# stm32_smart_teach.net
KiCad netlist of a schematic drawn in EasyEDA Pro
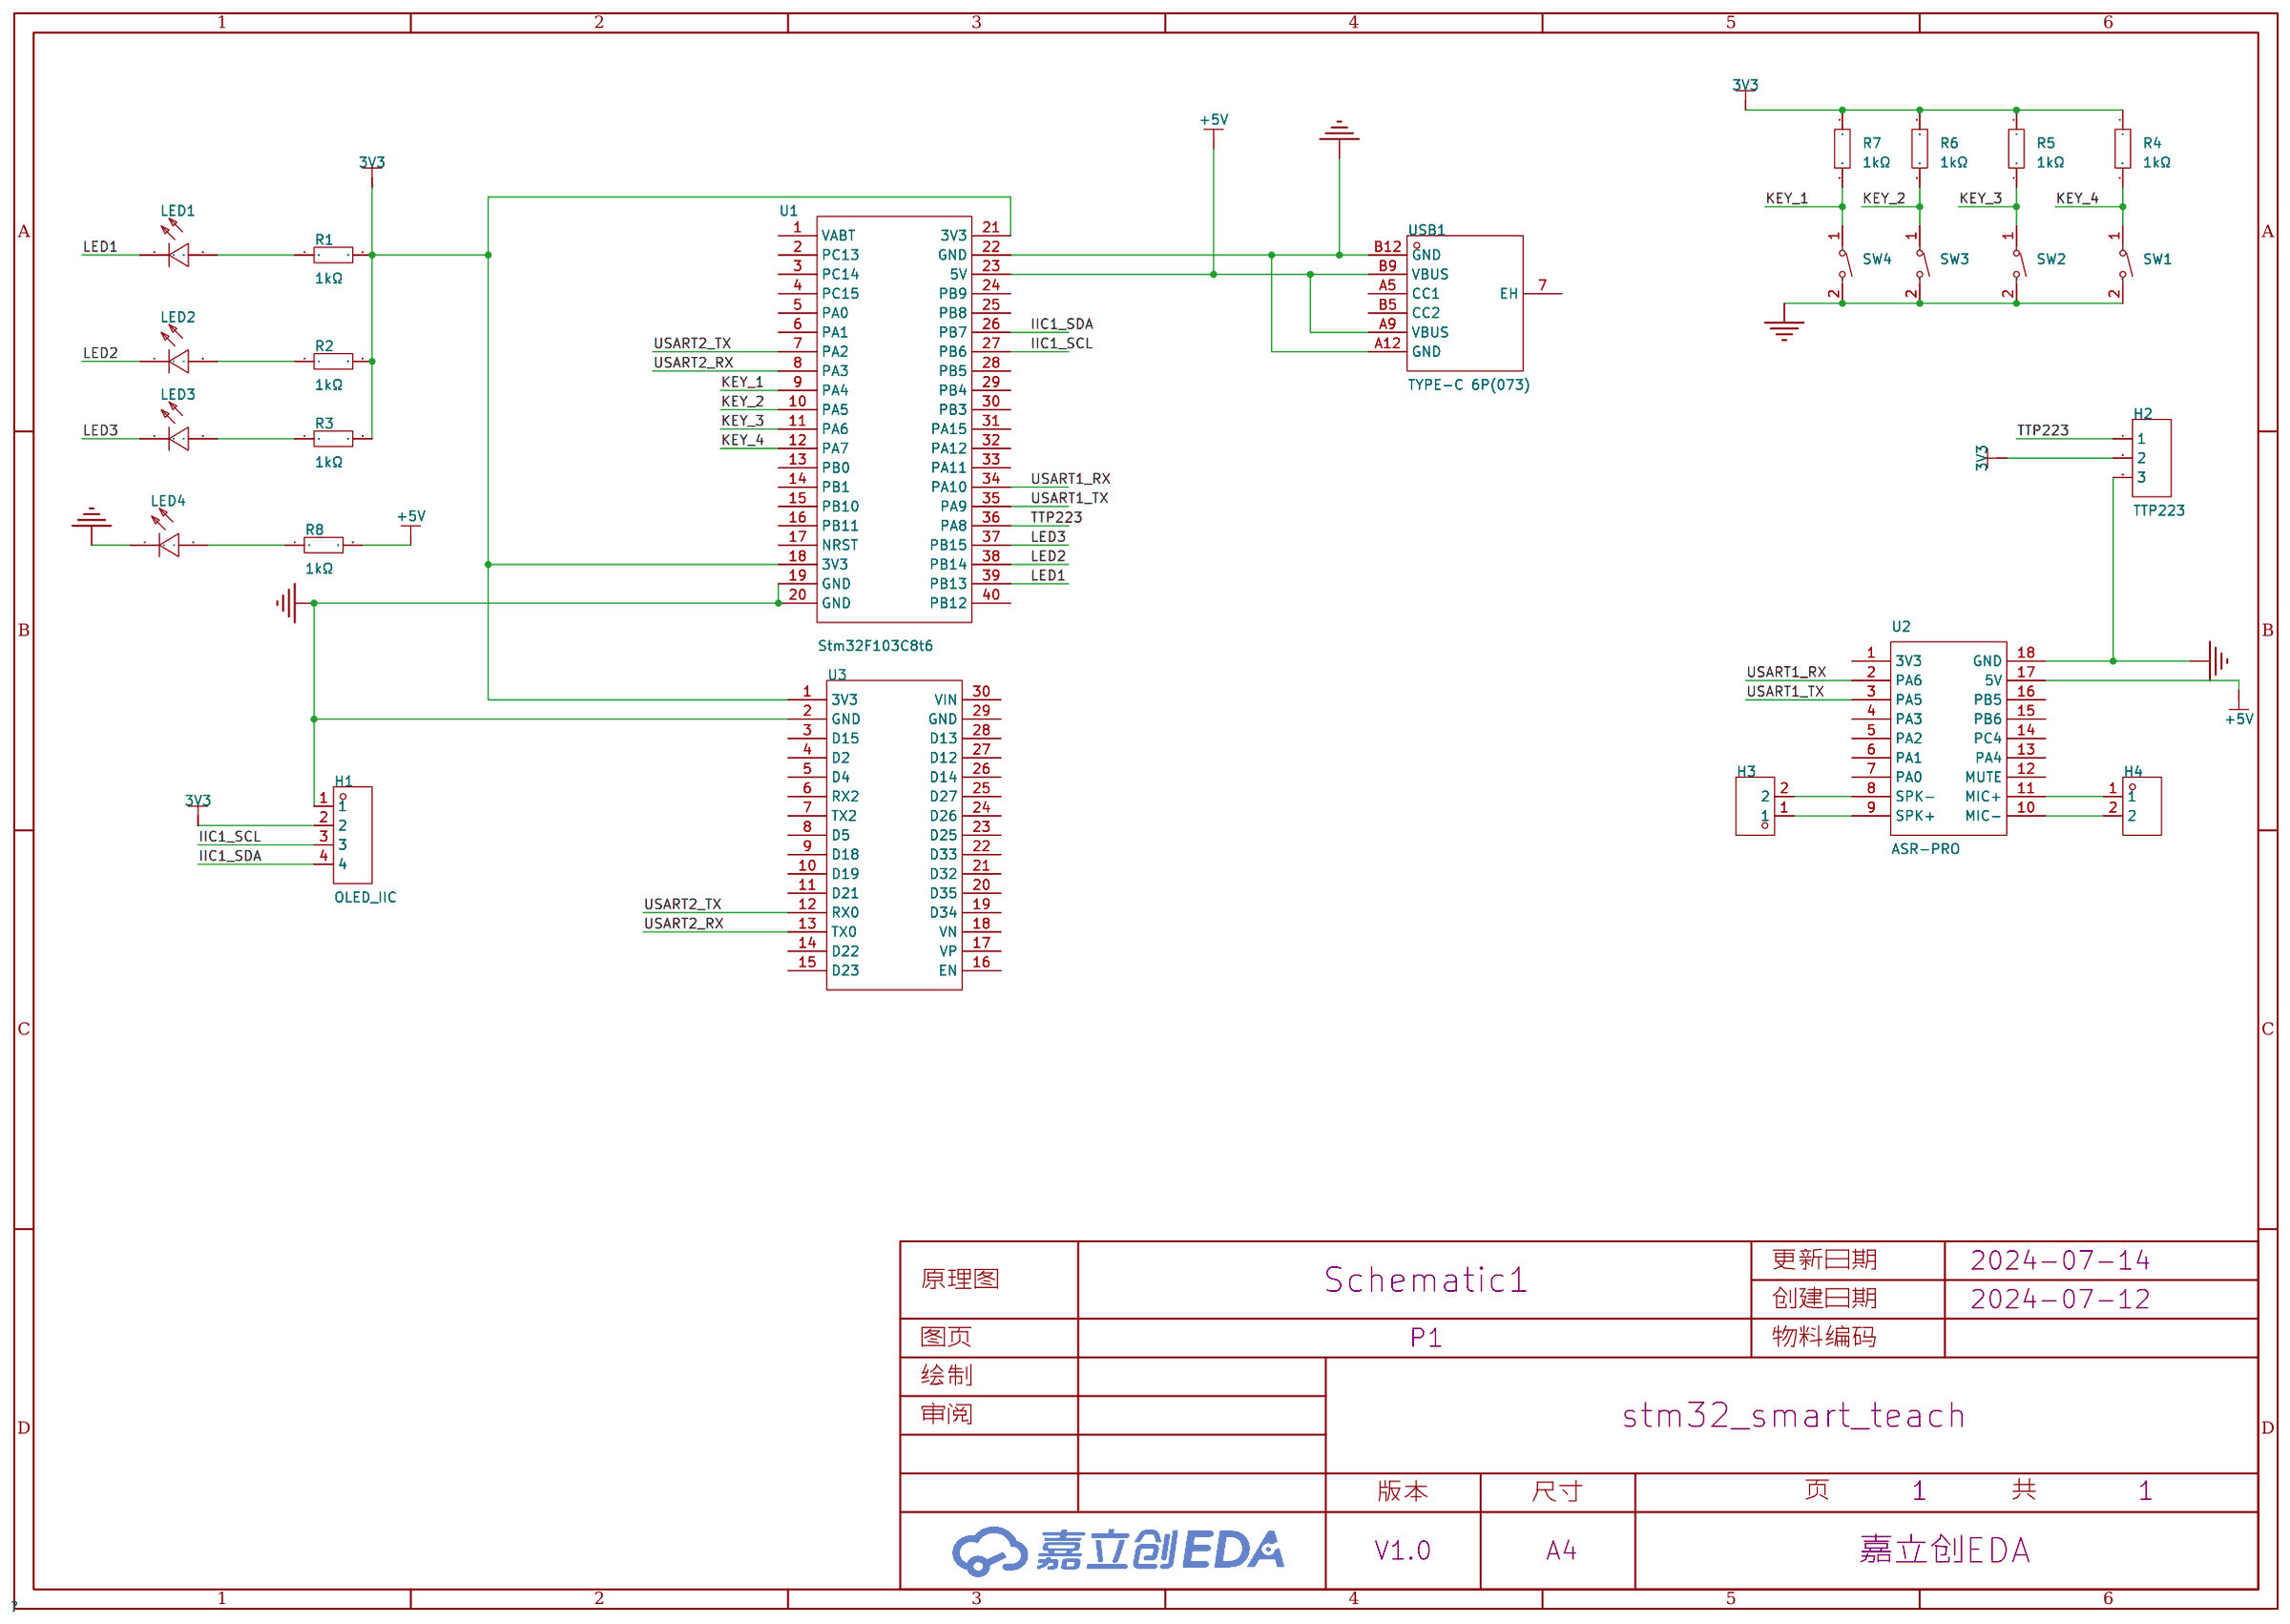
[diagram p0: schematic sheet]

(export (version "E")
  (design (tool "Eeschema 10.0.6"))
  (components
    (comp (ref "H1")
      (value "OLED_IIC")
      (footprint "easyedapro:HDR-TH_4P-P2.54-V-F")
      (fields (field (name "Manufacturer") "BOOMELE(博穆精密)"))
      (libsource (lib "easyedapro") (part "2.54-1*4P母"))
    )
    (comp (ref "H2")
      (value "TTP223")
      (footprint "easyedapro:HDR-TH_3P-P2.54-V-M-1")
      (fields (field (name "Manufacturer") "BOOMELE(博穆精密)"))
      (libsource (lib "easyedapro") (part "Header-Male-2.54_1x3"))
    )
    (comp (ref "H3")
      (value "PZ254V-11-02P")
      (footprint "easyedapro:HDR-TH_2P-P2.54-V-M")
      (fields (field (name "Manufacturer") "XFCN(兴飞)"))
      (libsource (lib "easyedapro") (part "PZ254V-11-02P"))
    )
    (comp (ref "H4")
      (value "PZ254V-11-02P")
      (footprint "easyedapro:HDR-TH_2P-P2.54-V-M")
      (fields (field (name "Manufacturer") "XFCN(兴飞)"))
      (libsource (lib "easyedapro") (part "PZ254V-11-02P"))
    )
    (comp (ref "LED1")
      (value "NCD0603R1")
      (footprint "easyedapro:LED0603-RD_RED")
      (fields (field (name "Manufacturer") "国星光电"))
      (libsource (lib "easyedapro") (part "FC-DA1608HRK-620D"))
    )
    (comp (ref "LED2")
      (value "NCD0603R1")
      (footprint "easyedapro:LED0603-RD_RED")
      (fields (field (name "Manufacturer") "国星光电"))
      (libsource (lib "easyedapro") (part "FC-DA1608HRK-620D"))
    )
    (comp (ref "LED3")
      (value "NCD0603R1")
      (footprint "easyedapro:LED0603-RD_RED")
      (fields (field (name "Manufacturer") "国星光电"))
      (libsource (lib "easyedapro") (part "FC-DA1608HRK-620D"))
    )
    (comp (ref "LED4")
      (value "NCD0603R1")
      (footprint "easyedapro:LED0603-RD_RED")
      (fields (field (name "Manufacturer") "国星光电"))
      (libsource (lib "easyedapro") (part "FC-DA1608HRK-620D"))
    )
    (comp (ref "R1")
      (value "1kΩ")
      (footprint "easyedapro:R0603")
      (description "电阻类型:厚膜电阻;阻值:1kΩ;精度:±1%;功率:100mW;最大工作电压:75V;温度系数:±100ppm/°C;")
      (fields
        (field (name "Manufacturer Part") "0603WAF1001T5E")
        (field (name "Manufacturer") "UNI-ROYAL(厚声)")
      )
      (libsource (lib "easyedapro") (part "0603WAF1001T5E"))
    )
    (comp (ref "R2")
      (value "1kΩ")
      (footprint "easyedapro:R0603")
      (description "电阻类型:厚膜电阻;阻值:1kΩ;精度:±1%;功率:100mW;最大工作电压:75V;温度系数:±100ppm/°C;")
      (fields
        (field (name "Manufacturer Part") "0603WAF1001T5E")
        (field (name "Manufacturer") "UNI-ROYAL(厚声)")
      )
      (libsource (lib "easyedapro") (part "0603WAF1001T5E"))
    )
    (comp (ref "R3")
      (value "1kΩ")
      (footprint "easyedapro:R0603")
      (description "电阻类型:厚膜电阻;阻值:1kΩ;精度:±1%;功率:100mW;最大工作电压:75V;温度系数:±100ppm/°C;")
      (fields
        (field (name "Manufacturer Part") "0603WAF1001T5E")
        (field (name "Manufacturer") "UNI-ROYAL(厚声)")
      )
      (libsource (lib "easyedapro") (part "0603WAF1001T5E"))
    )
    (comp (ref "R4")
      (value "1kΩ")
      (footprint "easyedapro:R0603")
      (description "电阻类型:厚膜电阻;阻值:1kΩ;精度:±1%;功率:100mW;最大工作电压:75V;温度系数:±100ppm/°C;")
      (fields
        (field (name "Manufacturer Part") "0603WAF1001T5E")
        (field (name "Manufacturer") "UNI-ROYAL(厚声)")
      )
      (libsource (lib "easyedapro") (part "0603WAF1001T5E"))
    )
    (comp (ref "R5")
      (value "1kΩ")
      (footprint "easyedapro:R0603")
      (description "电阻类型:厚膜电阻;阻值:1kΩ;精度:±1%;功率:100mW;最大工作电压:75V;温度系数:±100ppm/°C;")
      (fields
        (field (name "Manufacturer Part") "0603WAF1001T5E")
        (field (name "Manufacturer") "UNI-ROYAL(厚声)")
      )
      (libsource (lib "easyedapro") (part "0603WAF1001T5E"))
    )
    (comp (ref "R6")
      (value "1kΩ")
      (footprint "easyedapro:R0603")
      (description "电阻类型:厚膜电阻;阻值:1kΩ;精度:±1%;功率:100mW;最大工作电压:75V;温度系数:±100ppm/°C;")
      (fields
        (field (name "Manufacturer Part") "0603WAF1001T5E")
        (field (name "Manufacturer") "UNI-ROYAL(厚声)")
      )
      (libsource (lib "easyedapro") (part "0603WAF1001T5E"))
    )
    (comp (ref "R7")
      (value "1kΩ")
      (footprint "easyedapro:R0603")
      (description "电阻类型:厚膜电阻;阻值:1kΩ;精度:±1%;功率:100mW;最大工作电压:75V;温度系数:±100ppm/°C;")
      (fields
        (field (name "Manufacturer Part") "0603WAF1001T5E")
        (field (name "Manufacturer") "UNI-ROYAL(厚声)")
      )
      (libsource (lib "easyedapro") (part "0603WAF1001T5E"))
    )
    (comp (ref "R8")
      (value "1kΩ")
      (footprint "easyedapro:R0603")
      (description "电阻类型:厚膜电阻;阻值:1kΩ;精度:±1%;功率:100mW;最大工作电压:75V;温度系数:±100ppm/°C;")
      (fields
        (field (name "Manufacturer Part") "0603WAF1001T5E")
        (field (name "Manufacturer") "UNI-ROYAL(厚声)")
      )
      (libsource (lib "easyedapro") (part "0603WAF1001T5E"))
    )
    (comp (ref "SW1")
      (value "GT-TC060A-H025-L1S")
      (footprint "easyedapro:SW-SMD_L6.1-W3.5-LS8.0")
      (description "电路结构:单刀单掷;作用力:1.6N;安装方式:立贴;带支架:不带;触点电流:50mA;额定电压(AC):12V;额定电压(DC):12V;绝缘电阻:100MΩ;带灯:无;机械寿命:10万次;")
      (fields (field (name "Manufacturer") "G-Switch(品赞)"))
      (libsource (lib "easyedapro") (part "GT-TC060A-H025-L1S"))
    )
    (comp (ref "SW2")
      (value "GT-TC060A-H025-L1S")
      (footprint "easyedapro:SW-SMD_L6.1-W3.5-LS8.0")
      (description "电路结构:单刀单掷;作用力:1.6N;安装方式:立贴;带支架:不带;触点电流:50mA;额定电压(AC):12V;额定电压(DC):12V;绝缘电阻:100MΩ;带灯:无;机械寿命:10万次;")
      (fields (field (name "Manufacturer") "G-Switch(品赞)"))
      (libsource (lib "easyedapro") (part "GT-TC060A-H025-L1S"))
    )
    (comp (ref "SW3")
      (value "GT-TC060A-H025-L1S")
      (footprint "easyedapro:SW-SMD_L6.1-W3.5-LS8.0")
      (description "电路结构:单刀单掷;作用力:1.6N;安装方式:立贴;带支架:不带;触点电流:50mA;额定电压(AC):12V;额定电压(DC):12V;绝缘电阻:100MΩ;带灯:无;机械寿命:10万次;")
      (fields (field (name "Manufacturer") "G-Switch(品赞)"))
      (libsource (lib "easyedapro") (part "GT-TC060A-H025-L1S"))
    )
    (comp (ref "SW4")
      (value "GT-TC060A-H025-L1S")
      (footprint "easyedapro:SW-SMD_L6.1-W3.5-LS8.0")
      (description "电路结构:单刀单掷;作用力:1.6N;安装方式:立贴;带支架:不带;触点电流:50mA;额定电压(AC):12V;额定电压(DC):12V;绝缘电阻:100MΩ;带灯:无;机械寿命:10万次;")
      (fields (field (name "Manufacturer") "G-Switch(品赞)"))
      (libsource (lib "easyedapro") (part "GT-TC060A-H025-L1S"))
    )
    (comp (ref "U1") (value "Stm32F103C8t6") (libsource (lib "easyedapro") (part "stm32f103c8t6")))
    (comp (ref "U2") (value "ASR-PRO") (libsource (lib "easyedapro") (part "ASR-PRO")))
    (comp (ref "U3") (value "~") (libsource (lib "easyedapro") (part "esp32")))
    (comp (ref "USB1")
      (value "TYPE-C 6P(073)")
      (footprint "easyedapro:TYPE-C-SMD_TYPE-C-6P")
      (description "连接器类型:Type-C;标准:-;公母:母;端口数量:1;触点数量:6P;安装方式:卧贴;额定电流 - 电源:5A;工作温度范围:-25°C~+85°C;")
      (fields (field (name "Manufacturer") "SHOU HAN(首韩)"))
      (libsource (lib "easyedapro") (part "TYPE-C 6P(073)"))
    )
  )
  (nets
    (net (code "1") (name "+5V") (class "Default")
      (node (ref "R8") (pin "2") (pinfunction "2_2") (pintype "input"))
      (node (ref "U1") (pin "23") (pinfunction "5V_23") (pintype "input"))
      (node (ref "U2") (pin "17") (pinfunction "5V_17") (pintype "input"))
      (node (ref "USB1") (pin "A9") (pinfunction "VBUS_A9") (pintype "unspecified"))
      (node (ref "USB1") (pin "B9") (pinfunction "VBUS_B9") (pintype "unspecified"))
    )
    (net (code "2") (name "/IIC1_SCL") (class "Default")
      (node (ref "H1") (pin "3") (pinfunction "3_3") (pintype "unspecified"))
      (node (ref "U1") (pin "27") (pinfunction "PB6_27") (pintype "input"))
    )
    (net (code "3") (name "/IIC1_SDA") (class "Default")
      (node (ref "H1") (pin "4") (pinfunction "4_4") (pintype "unspecified"))
      (node (ref "U1") (pin "26") (pinfunction "PB7_26") (pintype "input"))
    )
    (net (code "4") (name "/KEY_1") (class "Default")
      (node (ref "R7") (pin "2") (pinfunction "2_2") (pintype "input"))
      (node (ref "SW4") (pin "1") (pinfunction "1_1") (pintype "unspecified"))
      (node (ref "U1") (pin "9") (pinfunction "PA4_9") (pintype "input"))
    )
    (net (code "5") (name "/KEY_2") (class "Default")
      (node (ref "R6") (pin "2") (pinfunction "2_2") (pintype "input"))
      (node (ref "SW3") (pin "1") (pinfunction "1_1") (pintype "unspecified"))
      (node (ref "U1") (pin "10") (pinfunction "PA5_10") (pintype "input"))
    )
    (net (code "6") (name "/KEY_3") (class "Default")
      (node (ref "R5") (pin "2") (pinfunction "2_2") (pintype "input"))
      (node (ref "SW2") (pin "1") (pinfunction "1_1") (pintype "unspecified"))
      (node (ref "U1") (pin "11") (pinfunction "PA6_11") (pintype "input"))
    )
    (net (code "7") (name "/KEY_4") (class "Default")
      (node (ref "R4") (pin "2") (pinfunction "2_2") (pintype "input"))
      (node (ref "SW1") (pin "1") (pinfunction "1_1") (pintype "unspecified"))
      (node (ref "U1") (pin "12") (pinfunction "PA7_12") (pintype "input"))
    )
    (net (code "8") (name "/LED1") (class "Default")
      (node (ref "LED1") (pin "1") (pinfunction "K_1") (pintype "input"))
      (node (ref "U1") (pin "39") (pinfunction "PB13_39") (pintype "input"))
    )
    (net (code "9") (name "/LED2") (class "Default")
      (node (ref "LED2") (pin "1") (pinfunction "K_1") (pintype "input"))
      (node (ref "U1") (pin "38") (pinfunction "PB14_38") (pintype "input"))
    )
    (net (code "10") (name "/LED3") (class "Default")
      (node (ref "LED3") (pin "1") (pinfunction "K_1") (pintype "input"))
      (node (ref "U1") (pin "37") (pinfunction "PB15_37") (pintype "input"))
    )
    (net (code "11") (name "/TTP223") (class "Default")
      (node (ref "H2") (pin "1") (pinfunction "1_1") (pintype "input"))
      (node (ref "U1") (pin "36") (pinfunction "PA8_36") (pintype "input"))
    )
    (net (code "12") (name "/USART1_RX") (class "Default")
      (node (ref "U1") (pin "34") (pinfunction "PA10_34") (pintype "input"))
      (node (ref "U2") (pin "2") (pinfunction "PA6_2") (pintype "input"))
    )
    (net (code "13") (name "/USART1_TX") (class "Default")
      (node (ref "U1") (pin "35") (pinfunction "PA9_35") (pintype "input"))
      (node (ref "U2") (pin "3") (pinfunction "PA5_3") (pintype "input"))
    )
    (net (code "14") (name "/USART2_RX") (class "Default")
      (node (ref "U1") (pin "8") (pinfunction "PA3_8") (pintype "input"))
      (node (ref "U3") (pin "13") (pinfunction "TX0_13") (pintype "input"))
    )
    (net (code "15") (name "/USART2_TX") (class "Default")
      (node (ref "U1") (pin "7") (pinfunction "PA2_7") (pintype "input"))
      (node (ref "U3") (pin "12") (pinfunction "RX0_12") (pintype "input"))
    )
    (net (code "16") (name "3V3") (class "Default")
      (node (ref "H1") (pin "2") (pinfunction "2_2") (pintype "unspecified"))
      (node (ref "H2") (pin "2") (pinfunction "2_2") (pintype "input"))
      (node (ref "R1") (pin "2") (pinfunction "2_2") (pintype "input"))
      (node (ref "R2") (pin "2") (pinfunction "2_2") (pintype "input"))
      (node (ref "R3") (pin "2") (pinfunction "2_2") (pintype "input"))
      (node (ref "R4") (pin "1") (pinfunction "1_1") (pintype "input"))
      (node (ref "R5") (pin "1") (pinfunction "1_1") (pintype "input"))
      (node (ref "R6") (pin "1") (pinfunction "1_1") (pintype "input"))
      (node (ref "R7") (pin "1") (pinfunction "1_1") (pintype "input"))
      (node (ref "U1") (pin "18") (pinfunction "3V3_18") (pintype "input"))
      (node (ref "U1") (pin "21") (pinfunction "3V3_21") (pintype "input"))
      (node (ref "U3") (pin "1") (pinfunction "3V3_1") (pintype "input"))
    )
    (net (code "17") (name "GND") (class "Default")
      (node (ref "H1") (pin "1") (pinfunction "1_1") (pintype "unspecified"))
      (node (ref "H2") (pin "3") (pinfunction "3_3") (pintype "input"))
      (node (ref "LED4") (pin "1") (pinfunction "K_1") (pintype "input"))
      (node (ref "SW1") (pin "2") (pinfunction "2_2") (pintype "unspecified"))
      (node (ref "SW2") (pin "2") (pinfunction "2_2") (pintype "unspecified"))
      (node (ref "SW3") (pin "2") (pinfunction "2_2") (pintype "unspecified"))
      (node (ref "SW4") (pin "2") (pinfunction "2_2") (pintype "unspecified"))
      (node (ref "U1") (pin "19") (pinfunction "GND_19") (pintype "input"))
      (node (ref "U1") (pin "20") (pinfunction "GND_20") (pintype "input"))
      (node (ref "U1") (pin "22") (pinfunction "GND_22") (pintype "input"))
      (node (ref "U2") (pin "18") (pinfunction "GND_18") (pintype "input"))
      (node (ref "U3") (pin "2") (pinfunction "GND_2") (pintype "input"))
      (node (ref "USB1") (pin "A12") (pinfunction "GND_A12") (pintype "unspecified"))
      (node (ref "USB1") (pin "B12") (pinfunction "GND_B12") (pintype "unspecified"))
    )
    (net (code "18") (name "Net-(LED1-A)") (class "Default")
      (node (ref "LED1") (pin "2") (pinfunction "A_2") (pintype "input"))
      (node (ref "R1") (pin "1") (pinfunction "1_1") (pintype "input"))
    )
    (net (code "19") (name "Net-(LED2-A)") (class "Default")
      (node (ref "LED2") (pin "2") (pinfunction "A_2") (pintype "input"))
      (node (ref "R2") (pin "1") (pinfunction "1_1") (pintype "input"))
    )
    (net (code "20") (name "Net-(LED3-A)") (class "Default")
      (node (ref "LED3") (pin "2") (pinfunction "A_2") (pintype "input"))
      (node (ref "R3") (pin "1") (pinfunction "1_1") (pintype "input"))
    )
    (net (code "21") (name "Net-(LED4-A)") (class "Default")
      (node (ref "LED4") (pin "2") (pinfunction "A_2") (pintype "input"))
      (node (ref "R8") (pin "1") (pinfunction "1_1") (pintype "input"))
    )
    (net (code "22") (name "Net-(U2-MIC+)") (class "Default")
      (node (ref "H4") (pin "1") (pinfunction "1_1") (pintype "unspecified"))
      (node (ref "U2") (pin "11") (pinfunction "MIC+_11") (pintype "input"))
    )
    (net (code "23") (name "Net-(U2-MIC-)") (class "Default")
      (node (ref "H4") (pin "2") (pinfunction "2_2") (pintype "unspecified"))
      (node (ref "U2") (pin "10") (pinfunction "MIC-_10") (pintype "input"))
    )
    (net (code "24") (name "Net-(U2-SPK+)") (class "Default")
      (node (ref "H3") (pin "1") (pinfunction "1_1") (pintype "unspecified"))
      (node (ref "U2") (pin "9") (pinfunction "SPK+_9") (pintype "input"))
    )
    (net (code "25") (name "Net-(U2-SPK-)") (class "Default")
      (node (ref "H3") (pin "2") (pinfunction "2_2") (pintype "unspecified"))
      (node (ref "U2") (pin "8") (pinfunction "SPK-_8") (pintype "input"))
    )
    (net (code "26") (name "unconnected-(U1-NRST-Pad17)") (class "Default")
      (node (ref "U1") (pin "17") (pinfunction "NRST_17") (pintype "input"))
    )
    (net (code "27") (name "unconnected-(U1-PA0-Pad5)") (class "Default")
      (node (ref "U1") (pin "5") (pinfunction "PA0_5") (pintype "input"))
    )
    (net (code "28") (name "unconnected-(U1-PA1-Pad6)") (class "Default")
      (node (ref "U1") (pin "6") (pinfunction "PA1_6") (pintype "input"))
    )
    (net (code "29") (name "unconnected-(U1-PA11-Pad33)") (class "Default")
      (node (ref "U1") (pin "33") (pinfunction "PA11_33") (pintype "input"))
    )
    (net (code "30") (name "unconnected-(U1-PA12-Pad32)") (class "Default")
      (node (ref "U1") (pin "32") (pinfunction "PA12_32") (pintype "input"))
    )
    (net (code "31") (name "unconnected-(U1-PA15-Pad31)") (class "Default")
      (node (ref "U1") (pin "31") (pinfunction "PA15_31") (pintype "input"))
    )
    (net (code "32") (name "unconnected-(U1-PB0-Pad13)") (class "Default")
      (node (ref "U1") (pin "13") (pinfunction "PB0_13") (pintype "input"))
    )
    (net (code "33") (name "unconnected-(U1-PB1-Pad14)") (class "Default")
      (node (ref "U1") (pin "14") (pinfunction "PB1_14") (pintype "input"))
    )
    (net (code "34") (name "unconnected-(U1-PB3-Pad30)") (class "Default")
      (node (ref "U1") (pin "30") (pinfunction "PB3_30") (pintype "input"))
    )
    (net (code "35") (name "unconnected-(U1-PB4-Pad29)") (class "Default")
      (node (ref "U1") (pin "29") (pinfunction "PB4_29") (pintype "input"))
    )
    (net (code "36") (name "unconnected-(U1-PB5-Pad28)") (class "Default")
      (node (ref "U1") (pin "28") (pinfunction "PB5_28") (pintype "input"))
    )
    (net (code "37") (name "unconnected-(U1-PB8-Pad25)") (class "Default")
      (node (ref "U1") (pin "25") (pinfunction "PB8_25") (pintype "input"))
    )
    (net (code "38") (name "unconnected-(U1-PB9-Pad24)") (class "Default")
      (node (ref "U1") (pin "24") (pinfunction "PB9_24") (pintype "input"))
    )
    (net (code "39") (name "unconnected-(U1-PB10-Pad15)") (class "Default")
      (node (ref "U1") (pin "15") (pinfunction "PB10_15") (pintype "input"))
    )
    (net (code "40") (name "unconnected-(U1-PB11-Pad16)") (class "Default")
      (node (ref "U1") (pin "16") (pinfunction "PB11_16") (pintype "input"))
    )
    (net (code "41") (name "unconnected-(U1-PB12-Pad40)") (class "Default")
      (node (ref "U1") (pin "40") (pinfunction "PB12_40") (pintype "input"))
    )
    (net (code "42") (name "unconnected-(U1-PC13-Pad2)") (class "Default")
      (node (ref "U1") (pin "2") (pinfunction "PC13_2") (pintype "input"))
    )
    (net (code "43") (name "unconnected-(U1-PC14-Pad3)") (class "Default")
      (node (ref "U1") (pin "3") (pinfunction "PC14_3") (pintype "input"))
    )
    (net (code "44") (name "unconnected-(U1-PC15-Pad4)") (class "Default")
      (node (ref "U1") (pin "4") (pinfunction "PC15_4") (pintype "input"))
    )
    (net (code "45") (name "unconnected-(U1-VABT-Pad1)") (class "Default")
      (node (ref "U1") (pin "1") (pinfunction "VABT_1") (pintype "input"))
    )
    (net (code "46") (name "unconnected-(U2-3V3-Pad1)") (class "Default")
      (node (ref "U2") (pin "1") (pinfunction "3V3_1") (pintype "input"))
    )
    (net (code "47") (name "unconnected-(U2-MUTE-Pad12)") (class "Default")
      (node (ref "U2") (pin "12") (pinfunction "MUTE_12") (pintype "input"))
    )
    (net (code "48") (name "unconnected-(U2-PA0-Pad7)") (class "Default")
      (node (ref "U2") (pin "7") (pinfunction "PA0_7") (pintype "input"))
    )
    (net (code "49") (name "unconnected-(U2-PA1-Pad6)") (class "Default")
      (node (ref "U2") (pin "6") (pinfunction "PA1_6") (pintype "input"))
    )
    (net (code "50") (name "unconnected-(U2-PA2-Pad5)") (class "Default")
      (node (ref "U2") (pin "5") (pinfunction "PA2_5") (pintype "input"))
    )
    (net (code "51") (name "unconnected-(U2-PA3-Pad4)") (class "Default")
      (node (ref "U2") (pin "4") (pinfunction "PA3_4") (pintype "input"))
    )
    (net (code "52") (name "unconnected-(U2-PA4-Pad13)") (class "Default")
      (node (ref "U2") (pin "13") (pinfunction "PA4_13") (pintype "input"))
    )
    (net (code "53") (name "unconnected-(U2-PB5-Pad16)") (class "Default")
      (node (ref "U2") (pin "16") (pinfunction "PB5_16") (pintype "input"))
    )
    (net (code "54") (name "unconnected-(U2-PB6-Pad15)") (class "Default")
      (node (ref "U2") (pin "15") (pinfunction "PB6_15") (pintype "input"))
    )
    (net (code "55") (name "unconnected-(U2-PC4-Pad14)") (class "Default")
      (node (ref "U2") (pin "14") (pinfunction "PC4_14") (pintype "input"))
    )
    (net (code "56") (name "unconnected-(U3-D2-Pad4)") (class "Default")
      (node (ref "U3") (pin "4") (pinfunction "D2_4") (pintype "input"))
    )
    (net (code "57") (name "unconnected-(U3-D4-Pad5)") (class "Default")
      (node (ref "U3") (pin "5") (pinfunction "D4_5") (pintype "input"))
    )
    (net (code "58") (name "unconnected-(U3-D5-Pad8)") (class "Default")
      (node (ref "U3") (pin "8") (pinfunction "D5_8") (pintype "input"))
    )
    (net (code "59") (name "unconnected-(U3-D12-Pad27)") (class "Default")
      (node (ref "U3") (pin "27") (pinfunction "D12_27") (pintype "input"))
    )
    (net (code "60") (name "unconnected-(U3-D13-Pad28)") (class "Default")
      (node (ref "U3") (pin "28") (pinfunction "D13_28") (pintype "input"))
    )
    (net (code "61") (name "unconnected-(U3-D14-Pad26)") (class "Default")
      (node (ref "U3") (pin "26") (pinfunction "D14_26") (pintype "input"))
    )
    (net (code "62") (name "unconnected-(U3-D15-Pad3)") (class "Default")
      (node (ref "U3") (pin "3") (pinfunction "D15_3") (pintype "input"))
    )
    (net (code "63") (name "unconnected-(U3-D18-Pad9)") (class "Default")
      (node (ref "U3") (pin "9") (pinfunction "D18_9") (pintype "input"))
    )
    (net (code "64") (name "unconnected-(U3-D19-Pad10)") (class "Default")
      (node (ref "U3") (pin "10") (pinfunction "D19_10") (pintype "input"))
    )
    (net (code "65") (name "unconnected-(U3-D21-Pad11)") (class "Default")
      (node (ref "U3") (pin "11") (pinfunction "D21_11") (pintype "input"))
    )
    (net (code "66") (name "unconnected-(U3-D22-Pad14)") (class "Default")
      (node (ref "U3") (pin "14") (pinfunction "D22_14") (pintype "input"))
    )
    (net (code "67") (name "unconnected-(U3-D23-Pad15)") (class "Default")
      (node (ref "U3") (pin "15") (pinfunction "D23_15") (pintype "input"))
    )
    (net (code "68") (name "unconnected-(U3-D25-Pad23)") (class "Default")
      (node (ref "U3") (pin "23") (pinfunction "D25_23") (pintype "input"))
    )
    (net (code "69") (name "unconnected-(U3-D26-Pad24)") (class "Default")
      (node (ref "U3") (pin "24") (pinfunction "D26_24") (pintype "input"))
    )
    (net (code "70") (name "unconnected-(U3-D27-Pad25)") (class "Default")
      (node (ref "U3") (pin "25") (pinfunction "D27_25") (pintype "input"))
    )
    (net (code "71") (name "unconnected-(U3-D32-Pad21)") (class "Default")
      (node (ref "U3") (pin "21") (pinfunction "D32_21") (pintype "input"))
    )
    (net (code "72") (name "unconnected-(U3-D33-Pad22)") (class "Default")
      (node (ref "U3") (pin "22") (pinfunction "D33_22") (pintype "input"))
    )
    (net (code "73") (name "unconnected-(U3-D34-Pad19)") (class "Default")
      (node (ref "U3") (pin "19") (pinfunction "D34_19") (pintype "input"))
    )
    (net (code "74") (name "unconnected-(U3-D35-Pad20)") (class "Default")
      (node (ref "U3") (pin "20") (pinfunction "D35_20") (pintype "input"))
    )
    (net (code "75") (name "unconnected-(U3-EN-Pad16)") (class "Default")
      (node (ref "U3") (pin "16") (pinfunction "EN_16") (pintype "input"))
    )
    (net (code "76") (name "unconnected-(U3-GND-Pad29)") (class "Default")
      (node (ref "U3") (pin "29") (pinfunction "GND_29") (pintype "input"))
    )
    (net (code "77") (name "unconnected-(U3-RX2-Pad6)") (class "Default")
      (node (ref "U3") (pin "6") (pinfunction "RX2_6") (pintype "input"))
    )
    (net (code "78") (name "unconnected-(U3-TX2-Pad7)") (class "Default")
      (node (ref "U3") (pin "7") (pinfunction "TX2_7") (pintype "input"))
    )
    (net (code "79") (name "unconnected-(U3-VIN-Pad30)") (class "Default")
      (node (ref "U3") (pin "30") (pinfunction "VIN_30") (pintype "input"))
    )
    (net (code "80") (name "unconnected-(U3-VN-Pad18)") (class "Default")
      (node (ref "U3") (pin "18") (pinfunction "VN_18") (pintype "input"))
    )
    (net (code "81") (name "unconnected-(U3-VP-Pad17)") (class "Default")
      (node (ref "U3") (pin "17") (pinfunction "VP_17") (pintype "input"))
    )
    (net (code "82") (name "unconnected-(USB1-CC1-PadA5)") (class "Default")
      (node (ref "USB1") (pin "A5") (pinfunction "CC1_A5") (pintype "unspecified"))
    )
    (net (code "83") (name "unconnected-(USB1-CC2-PadB5)") (class "Default")
      (node (ref "USB1") (pin "B5") (pinfunction "CC2_B5") (pintype "unspecified"))
    )
    (net (code "84") (name "unconnected-(USB1-EH-Pad7)") (class "Default")
      (node (ref "USB1") (pin "7") (pinfunction "EH_7") (pintype "unspecified"))
    )
  )
)
